# warship_demo_3.net
KiCad netlist of a schematic drawn in Altium Designer
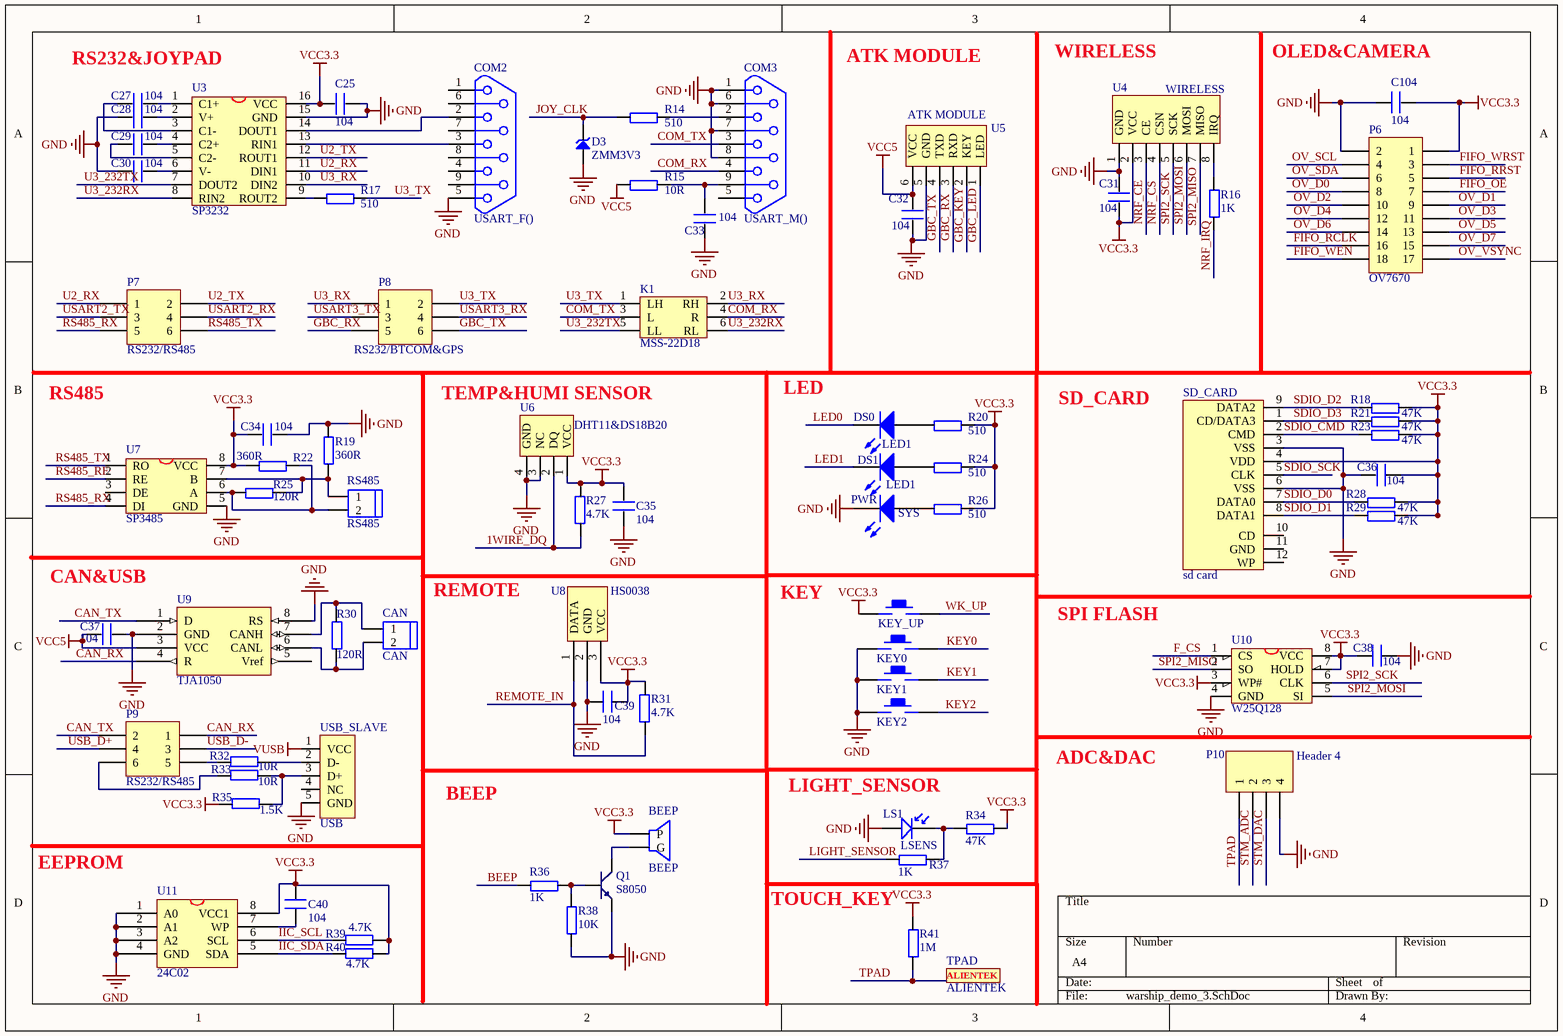
[diagram p0: warship_demo_3.SchDoc]

(export (version "E")
  (design (tool "Eeschema 10.0.6"))
  (components
    (comp (ref "BEEP")
      (value "BEEP")
      (footprint "BELL-5")
      (libsource (lib "WarShip V3 STM32103封装库") (part "BEEP"))
    )
    (comp (ref "C25") (value "104") (footprint "0603P") (libsource (lib "WarShip V3 STM32103封装库") (part "C")))
    (comp (ref "C27") (value "104") (footprint "0603P") (libsource (lib "WarShip V3 STM32103封装库") (part "C")))
    (comp (ref "C28") (value "104") (footprint "0603P") (libsource (lib "WarShip V3 STM32103封装库") (part "C")))
    (comp (ref "C29") (value "104") (footprint "0603P") (libsource (lib "WarShip V3 STM32103封装库") (part "C")))
    (comp (ref "C30") (value "104") (footprint "0603P") (libsource (lib "WarShip V3 STM32103封装库") (part "C")))
    (comp (ref "C31") (value "104") (footprint "0603P") (libsource (lib "WarShip V3 STM32103封装库") (part "C")))
    (comp (ref "C32") (value "104") (footprint "0603P") (libsource (lib "WarShip V3 STM32103封装库") (part "C")))
    (comp (ref "C33") (value "104") (footprint "0603P") (libsource (lib "WarShip V3 STM32103封装库") (part "C")))
    (comp (ref "C34") (value "104") (footprint "0603P") (libsource (lib "WarShip V3 STM32103封装库") (part "C")))
    (comp (ref "C35") (value "104") (footprint "0603P") (libsource (lib "WarShip V3 STM32103封装库") (part "C")))
    (comp (ref "C36") (value "104") (footprint "0603P") (libsource (lib "WarShip V3 STM32103封装库") (part "C")))
    (comp (ref "C37") (value "104") (footprint "0603P") (libsource (lib "WarShip V3 STM32103封装库") (part "C")))
    (comp (ref "C38") (value "104") (footprint "0603P") (libsource (lib "WarShip V3 STM32103封装库") (part "C")))
    (comp (ref "C39") (value "104") (footprint "0603P") (libsource (lib "WarShip V3 STM32103封装库") (part "C")))
    (comp (ref "C40") (value "104") (footprint "0603P") (libsource (lib "WarShip V3 STM32103封装库") (part "C")))
    (comp (ref "C104")
      (value "104")
      (footprint "0603P")
      (libsource (lib "WarShip V3 STM32103封装库") (part "C"))
    )
    (comp (ref "CAN")
      (value "CAN")
      (footprint "HEAD2L-0.8")
      (libsource (lib "WarShip V3 STM32103封装库") (part "HEAD2"))
    )
    (comp (ref "COM2")
      (value "USART_F()")
      (footprint "DB9")
      (libsource (lib "WarShip V3 STM32103封装库") (part "DB9"))
    )
    (comp (ref "COM3")
      (value "USART_M()")
      (footprint "DB9")
      (libsource (lib "WarShip V3 STM32103封装库") (part "DB9"))
    )
    (comp (ref "D3")
      (value "ZMM3V3")
      (footprint "DIODE_ZMMx")
      (description "ZMM3V6")
      (libsource (lib "WarShip V3 STM32103封装库") (part "ZMM3V6"))
    )
    (comp (ref "DS0")
      (value "LED1")
      (footprint "SMDLED")
      (description "Typical RED, GREEN, YELLOW, AMBER GaAs LED")
      (fields (field (name "PUBLISHER") "Altium Limited"))
      (libsource (lib "WarShip V3 STM32103封装库") (part "LED2"))
    )
    (comp (ref "DS1")
      (value "LED1")
      (footprint "SMDLED")
      (description "Typical RED, GREEN, YELLOW, AMBER GaAs LED")
      (fields (field (name "PUBLISHER") "Altium Limited"))
      (libsource (lib "WarShip V3 STM32103封装库") (part "LED2"))
    )
    (comp (ref "K1")
      (value "MSS-22D18")
      (footprint "MSS-22D18-DIP")
      (description "六脚波动开关")
      (libsource (lib "WarShip V3 STM32103封装库") (part "MSS-22D18"))
    )
    (comp (ref "KEY0")
      (value "KEY_UP")
      (footprint "KEY_M")
      (libsource (lib "WarShip V3 STM32103封装库") (part "KEY_M"))
    )
    (comp (ref "KEY1")
      (value "KEY_UP")
      (footprint "KEY_M")
      (libsource (lib "WarShip V3 STM32103封装库") (part "KEY_M"))
    )
    (comp (ref "KEY2")
      (value "KEY_UP")
      (footprint "KEY_M")
      (libsource (lib "WarShip V3 STM32103封装库") (part "KEY_M"))
    )
    (comp (ref "KEY_UP")
      (value "KEY_UP")
      (footprint "KEY_M")
      (libsource (lib "WarShip V3 STM32103封装库") (part "KEY_M"))
    )
    (comp (ref "LS1")
      (value "LSENS")
      (footprint "SMDLED")
      (description "LIGHT SENS")
      (libsource (lib "WarShip V3 STM32103封装库") (part "LSENS"))
    )
    (comp (ref "P6")
      (value "OV7670")
      (footprint "HDR2X9")
      (description "Header, 9-Pin, Dual row")
      (fields (field (name "PUBLISHER") "Altium Limited"))
      (libsource (lib "WarShip V3 STM32103封装库") (part "Header 9X2"))
    )
    (comp (ref "P7")
      (value "RS232/RS485")
      (footprint "HDR2X3")
      (description "Header, 3-Pin, Dual row")
      (fields (field (name "PUBLISHER") "Altium Limited"))
      (libsource (lib "WarShip V3 STM32103封装库") (part "Header 3X2"))
    )
    (comp (ref "P8")
      (value "RS232/BTCOM&GPS")
      (footprint "HDR2X3")
      (description "Header, 3-Pin, Dual row")
      (fields (field (name "PUBLISHER") "Altium Limited"))
      (libsource (lib "WarShip V3 STM32103封装库") (part "Header 3X2"))
    )
    (comp (ref "P9")
      (value "RS232/RS485")
      (footprint "HDR2X3")
      (description "Header, 3-Pin, Dual row")
      (fields (field (name "PUBLISHER") "Altium Limited"))
      (libsource (lib "") (part "Header 3X2_1"))
    )
    (comp (ref "P10")
      (value "Header 4")
      (footprint "HDR1X4")
      (description "Header, 4-Pin")
      (fields (field (name "PUBLISHER") "Altium Limited"))
      (libsource (lib "WarShip V3 STM32103封装库") (part "Header 4"))
    )
    (comp (ref "PWR")
      (value "SYS")
      (footprint "SMDLED")
      (description "Typical RED, GREEN, YELLOW, AMBER GaAs LED")
      (fields (field (name "PUBLISHER") "Altium Limited"))
      (libsource (lib "WarShip V3 STM32103封装库") (part "LED2"))
    )
    (comp (ref "Q1")
      (value "S8050")
      (footprint "SOT-23R")
      (description "8050/BCW846/BCW847")
      (libsource (lib "WarShip V3 STM32103封装库") (part "NPN"))
    )
    (comp (ref "R14") (value "510") (footprint "0603P") (libsource (lib "WarShip V3 STM32103封装库") (part "R")))
    (comp (ref "R15") (value "10R") (footprint "0603P") (libsource (lib "WarShip V3 STM32103封装库") (part "R")))
    (comp (ref "R16") (value "1K") (footprint "0603P") (libsource (lib "WarShip V3 STM32103封装库") (part "R")))
    (comp (ref "R17") (value "510") (footprint "0603P") (libsource (lib "WarShip V3 STM32103封装库") (part "R")))
    (comp (ref "R18") (value "47K") (footprint "0603P") (libsource (lib "WarShip V3 STM32103封装库") (part "R")))
    (comp (ref "R19")
      (value "360R")
      (footprint "0603P")
      (libsource (lib "WarShip V3 STM32103封装库") (part "R"))
    )
    (comp (ref "R20") (value "510") (footprint "0603P") (libsource (lib "WarShip V3 STM32103封装库") (part "R")))
    (comp (ref "R21") (value "47K") (footprint "0603P") (libsource (lib "WarShip V3 STM32103封装库") (part "R")))
    (comp (ref "R22")
      (value "360R")
      (footprint "0603P")
      (libsource (lib "WarShip V3 STM32103封装库") (part "R"))
    )
    (comp (ref "R23") (value "47K") (footprint "0603P") (libsource (lib "WarShip V3 STM32103封装库") (part "R")))
    (comp (ref "R24") (value "510") (footprint "0603P") (libsource (lib "WarShip V3 STM32103封装库") (part "R")))
    (comp (ref "R25")
      (value "120R")
      (footprint "0603P")
      (libsource (lib "WarShip V3 STM32103封装库") (part "R"))
    )
    (comp (ref "R26") (value "510") (footprint "0603P") (libsource (lib "WarShip V3 STM32103封装库") (part "R")))
    (comp (ref "R27")
      (value "4.7K")
      (footprint "0603P")
      (libsource (lib "WarShip V3 STM32103封装库") (part "R"))
    )
    (comp (ref "R28") (value "47K") (footprint "0603P") (libsource (lib "WarShip V3 STM32103封装库") (part "R")))
    (comp (ref "R29") (value "47K") (footprint "0603P") (libsource (lib "WarShip V3 STM32103封装库") (part "R")))
    (comp (ref "R30")
      (value "120R")
      (footprint "0603P")
      (libsource (lib "WarShip V3 STM32103封装库") (part "R"))
    )
    (comp (ref "R31")
      (value "4.7K")
      (footprint "0603P")
      (libsource (lib "WarShip V3 STM32103封装库") (part "R"))
    )
    (comp (ref "R32") (value "10R") (footprint "0603P") (libsource (lib "WarShip V3 STM32103封装库") (part "R")))
    (comp (ref "R33") (value "10R") (footprint "0603P") (libsource (lib "WarShip V3 STM32103封装库") (part "R")))
    (comp (ref "R34") (value "47K") (footprint "0603P") (libsource (lib "WarShip V3 STM32103封装库") (part "R")))
    (comp (ref "R35")
      (value "1.5K")
      (footprint "0603P")
      (libsource (lib "WarShip V3 STM32103封装库") (part "R"))
    )
    (comp (ref "R36") (value "1K") (footprint "0603P") (libsource (lib "WarShip V3 STM32103封装库") (part "R")))
    (comp (ref "R37") (value "1K") (footprint "0603P") (libsource (lib "WarShip V3 STM32103封装库") (part "R")))
    (comp (ref "R38") (value "10K") (footprint "0603P") (libsource (lib "WarShip V3 STM32103封装库") (part "R")))
    (comp (ref "R39")
      (value "4.7K")
      (footprint "0603P")
      (libsource (lib "WarShip V3 STM32103封装库") (part "R"))
    )
    (comp (ref "R40")
      (value "4.7K")
      (footprint "0603P")
      (libsource (lib "WarShip V3 STM32103封装库") (part "R"))
    )
    (comp (ref "R41") (value "1M") (footprint "0603P") (libsource (lib "WarShip V3 STM32103封装库") (part "R")))
    (comp (ref "RS485")
      (value "RS485")
      (footprint "HEAD2L-0.8")
      (libsource (lib "WarShip V3 STM32103封装库") (part "HEAD2"))
    )
    (comp (ref "SD_CARD")
      (value "sd card")
      (footprint "SDCARD_L")
      (libsource (lib "WarShip V3 STM32103封装库") (part "sd card"))
    )
    (comp (ref "TPAD")
      (value "ALIENTEK")
      (footprint "ALIENTEK_PAD1")
      (libsource (lib "WarShip V3 STM32103封装库") (part "ALIENTEK"))
    )
    (comp (ref "U3")
      (value "SP3232")
      (footprint "SOP16M")
      (libsource (lib "WarShip V3 STM32103封装库") (part "MAX3232"))
    )
    (comp (ref "U4")
      (value "WIRELESS")
      (footprint "NRF24L01")
      (libsource (lib "WarShip V3 STM32103封装库") (part "NRF24L01"))
    )
    (comp (ref "U5")
      (value "ATK MODULE")
      (footprint "HEAD6")
      (description "ATK-HC05")
      (libsource (lib "WarShip V3 STM32103封装库") (part "ATK-HC05"))
    )
    (comp (ref "U6")
      (value "DHT11&DS18B20")
      (footprint "DHT11")
      (description "数字温湿度传感器")
      (libsource (lib "WarShip V3 STM32103封装库") (part "DHT11"))
    )
    (comp (ref "U7")
      (value "SP3485")
      (footprint "SOP-8")
      (libsource (lib "WarShip V3 STM32103封装库") (part "MAX3485"))
    )
    (comp (ref "U8")
      (value "HS0038")
      (footprint "HS0038")
      (libsource (lib "WarShip V3 STM32103封装库") (part "HS0038"))
    )
    (comp (ref "U9")
      (value "TJA1050")
      (footprint "SOP-8")
      (libsource (lib "WarShip V3 STM32103封装库") (part "SN65HVD230D"))
    )
    (comp (ref "U10")
      (value "W25Q128")
      (footprint "SOIC-8")
      (description "W25X16;SST25VF016;MX25L1605")
      (libsource (lib "WarShip V3 STM32103封装库") (part "W25X16"))
    )
    (comp (ref "U11")
      (value "24C02")
      (footprint "SOP-8")
      (libsource (lib "WarShip V3 STM32103封装库") (part "24C256"))
    )
    (comp (ref "USB_SLAVE")
      (value "USB")
      (footprint "USB/SM0.8-6H5")
      (libsource (lib "WarShip V3 STM32103封装库") (part "USB5"))
    )
  )
  (nets
    (net (code "1") (name "/1WIRE_DQ") (class "Default")
      (node (ref "R27") (pin "2") (pintype "passive"))
      (node (ref "U6") (pin "2") (pinfunction "DQ_2") (pintype "passive"))
    )
    (net (code "2") (name "/BEEP") (class "Default") (node (ref "R36") (pin "1") (pintype "passive")))
    (net (code "3") (name "/CAN_RX") (class "Default")
      (node (ref "P9") (pin "1") (pinfunction "1_1") (pintype "passive"))
      (node (ref "U9") (pin "4") (pinfunction "R_4") (pintype "output"))
    )
    (net (code "4") (name "/CAN_TX") (class "Default")
      (node (ref "P9") (pin "2") (pinfunction "2_2") (pintype "passive"))
      (node (ref "U9") (pin "1") (pinfunction "D_1") (pintype "input"))
    )
    (net (code "5") (name "/COM_RX") (class "Default")
      (node (ref "COM3") (pin "4") (pinfunction "4_4") (pintype "passive"))
      (node (ref "K1") (pin "4") (pinfunction "R_4") (pintype "passive"))
    )
    (net (code "6") (name "/COM_TX") (class "Default")
      (node (ref "COM3") (pin "3") (pinfunction "3_3") (pintype "passive"))
      (node (ref "K1") (pin "3") (pinfunction "L_3") (pintype "passive"))
    )
    (net (code "7") (name "/FIFO_OE") (class "Default")
      (node (ref "P6") (pin "7") (pinfunction "7_7") (pintype "passive"))
    )
    (net (code "8") (name "/FIFO_RCLK") (class "Default")
      (node (ref "P6") (pin "16") (pinfunction "16_16") (pintype "passive"))
    )
    (net (code "9") (name "/FIFO_RRST") (class "Default")
      (node (ref "P6") (pin "5") (pinfunction "5_5") (pintype "passive"))
    )
    (net (code "10") (name "/FIFO_WEN") (class "Default")
      (node (ref "P6") (pin "18") (pinfunction "18_18") (pintype "passive"))
    )
    (net (code "11") (name "/FIFO_WRST") (class "Default")
      (node (ref "P6") (pin "3") (pinfunction "3_3") (pintype "passive"))
    )
    (net (code "12") (name "/F_CS") (class "Default")
      (node (ref "U10") (pin "1") (pinfunction "CS_1") (pintype "passive"))
    )
    (net (code "13") (name "/GBC_KEY") (class "Default")
      (node (ref "U5") (pin "2") (pinfunction "KEY_2") (pintype "passive"))
    )
    (net (code "14") (name "/GBC_LED") (class "Default")
      (node (ref "U5") (pin "1") (pinfunction "LED_1") (pintype "passive"))
    )
    (net (code "15") (name "/GBC_RX") (class "Default")
      (node (ref "P8") (pin "5") (pinfunction "5_5") (pintype "passive"))
      (node (ref "U5") (pin "3") (pinfunction "RXD_3") (pintype "passive"))
    )
    (net (code "16") (name "/GBC_TX") (class "Default")
      (node (ref "P8") (pin "6") (pinfunction "6_6") (pintype "passive"))
      (node (ref "U5") (pin "4") (pinfunction "TXD_4") (pintype "passive"))
    )
    (net (code "17") (name "/IIC_SCL") (class "Default")
      (node (ref "R39") (pin "2") (pintype "passive"))
      (node (ref "U11") (pin "6") (pinfunction "SCL_6") (pintype "passive"))
    )
    (net (code "18") (name "/IIC_SDA") (class "Default")
      (node (ref "R40") (pin "2") (pintype "passive"))
      (node (ref "U11") (pin "5") (pinfunction "SDA_5") (pintype "passive"))
    )
    (net (code "19") (name "/JOY_CLK") (class "Default")
      (node (ref "D3") (pin "2") (pintype "passive"))
      (node (ref "R14") (pin "1") (pintype "passive"))
    )
    (net (code "20") (name "/KEY0") (class "Default")
      (node (ref "KEY0") (pin "2") (pinfunction "2_2") (pintype "passive"))
    )
    (net (code "21") (name "/KEY1") (class "Default")
      (node (ref "KEY1") (pin "2") (pinfunction "2_2") (pintype "passive"))
    )
    (net (code "22") (name "/KEY2") (class "Default")
      (node (ref "KEY2") (pin "2") (pinfunction "2_2") (pintype "passive"))
    )
    (net (code "23") (name "/LED0") (class "Default")
      (node (ref "DS0") (pin "2") (pinfunction "K_2") (pintype "passive"))
    )
    (net (code "24") (name "/LED1") (class "Default")
      (node (ref "DS1") (pin "2") (pinfunction "K_2") (pintype "passive"))
    )
    (net (code "25") (name "/LIGHT_SENSOR") (class "Default")
      (node (ref "R37") (pin "1") (pintype "passive"))
    )
    (net (code "26") (name "/NRF_CE") (class "Default")
      (node (ref "U4") (pin "3") (pinfunction "CE_3") (pintype "passive"))
    )
    (net (code "27") (name "/NRF_CS") (class "Default")
      (node (ref "U4") (pin "4") (pinfunction "CSN_4") (pintype "passive"))
    )
    (net (code "28") (name "/NRF_IRQ") (class "Default") (node (ref "R16") (pin "1") (pintype "passive")))
    (net (code "29") (name "/OV_D0") (class "Default")
      (node (ref "P6") (pin "8") (pinfunction "8_8") (pintype "passive"))
    )
    (net (code "30") (name "/OV_D1") (class "Default")
      (node (ref "P6") (pin "9") (pinfunction "9_9") (pintype "passive"))
    )
    (net (code "31") (name "/OV_D2") (class "Default")
      (node (ref "P6") (pin "10") (pinfunction "10_10") (pintype "passive"))
    )
    (net (code "32") (name "/OV_D3") (class "Default")
      (node (ref "P6") (pin "11") (pinfunction "11_11") (pintype "passive"))
    )
    (net (code "33") (name "/OV_D4") (class "Default")
      (node (ref "P6") (pin "12") (pinfunction "12_12") (pintype "passive"))
    )
    (net (code "34") (name "/OV_D5") (class "Default")
      (node (ref "P6") (pin "13") (pinfunction "13_13") (pintype "passive"))
    )
    (net (code "35") (name "/OV_D6") (class "Default")
      (node (ref "P6") (pin "14") (pinfunction "14_14") (pintype "passive"))
    )
    (net (code "36") (name "/OV_D7") (class "Default")
      (node (ref "P6") (pin "15") (pinfunction "15_15") (pintype "passive"))
    )
    (net (code "37") (name "/OV_SCL") (class "Default")
      (node (ref "P6") (pin "4") (pinfunction "4_4") (pintype "passive"))
    )
    (net (code "38") (name "/OV_SDA") (class "Default")
      (node (ref "P6") (pin "6") (pinfunction "6_6") (pintype "passive"))
    )
    (net (code "39") (name "/OV_VSYNC") (class "Default")
      (node (ref "P6") (pin "17") (pinfunction "17_17") (pintype "passive"))
    )
    (net (code "40") (name "/REMOTE_IN") (class "Default")
      (node (ref "R31") (pin "2") (pintype "passive"))
      (node (ref "U8") (pin "1") (pinfunction "DATA_1") (pintype "passive"))
    )
    (net (code "41") (name "/RS485_RE") (class "Default")
      (node (ref "U7") (pin "2") (pinfunction "RE_2") (pintype "passive"))
    )
    (net (code "42") (name "/RS485_RX") (class "Default")
      (node (ref "P7") (pin "5") (pinfunction "5_5") (pintype "passive"))
      (node (ref "U7") (pin "4") (pinfunction "DI_4") (pintype "passive"))
    )
    (net (code "43") (name "/RS485_TX") (class "Default")
      (node (ref "P7") (pin "6") (pinfunction "6_6") (pintype "passive"))
      (node (ref "U7") (pin "1") (pinfunction "RO_1") (pintype "passive"))
    )
    (net (code "44") (name "/SDIO_CMD") (class "Default")
      (node (ref "R23") (pin "1") (pintype "passive"))
      (node (ref "SD_CARD") (pin "2") (pinfunction "CMD_2") (pintype "passive"))
    )
    (net (code "45") (name "/SDIO_D0") (class "Default")
      (node (ref "R28") (pin "1") (pintype "passive"))
      (node (ref "SD_CARD") (pin "7") (pinfunction "DATA0_7") (pintype "passive"))
    )
    (net (code "46") (name "/SDIO_D1") (class "Default")
      (node (ref "R29") (pin "1") (pintype "passive"))
      (node (ref "SD_CARD") (pin "8") (pinfunction "DATA1_8") (pintype "passive"))
    )
    (net (code "47") (name "/SDIO_D2") (class "Default")
      (node (ref "R18") (pin "1") (pintype "passive"))
      (node (ref "SD_CARD") (pin "9") (pinfunction "DATA2_9") (pintype "passive"))
    )
    (net (code "48") (name "/SDIO_D3") (class "Default")
      (node (ref "R21") (pin "1") (pintype "passive"))
      (node (ref "SD_CARD") (pin "1") (pinfunction "CD/DATA3_1") (pintype "passive"))
    )
    (net (code "49") (name "/SDIO_SCK") (class "Default")
      (node (ref "SD_CARD") (pin "5") (pinfunction "CLK_5") (pintype "passive"))
    )
    (net (code "50") (name "/SPI2_MISO") (class "Default")
      (node (ref "U10") (pin "2") (pinfunction "SO_2") (pintype "passive"))
      (node (ref "U4") (pin "7") (pinfunction "MISO_7") (pintype "passive"))
    )
    (net (code "51") (name "/SPI2_MOSI") (class "Default")
      (node (ref "U10") (pin "5") (pinfunction "SI_5") (pintype "passive"))
      (node (ref "U4") (pin "6") (pinfunction "MOSI_6") (pintype "passive"))
    )
    (net (code "52") (name "/SPI2_SCK") (class "Default")
      (node (ref "U10") (pin "6") (pinfunction "CLK_6") (pintype "passive"))
      (node (ref "U4") (pin "5") (pinfunction "SCK_5") (pintype "passive"))
    )
    (net (code "53") (name "/STM_ADC") (class "Default")
      (node (ref "P10") (pin "2") (pinfunction "2_2") (pintype "passive"))
    )
    (net (code "54") (name "/STM_DAC") (class "Default")
      (node (ref "P10") (pin "3") (pinfunction "3_3") (pintype "passive"))
    )
    (net (code "55") (name "/TPAD") (class "Default")
      (node (ref "P10") (pin "1") (pinfunction "1_1") (pintype "passive"))
      (node (ref "R41") (pin "1") (pintype "passive"))
    )
    (net (code "56") (name "/U2_RX") (class "Default")
      (node (ref "P7") (pin "1") (pinfunction "1_1") (pintype "passive"))
      (node (ref "U3") (pin "11") (pinfunction "DIN1_11") (pintype "passive"))
    )
    (net (code "57") (name "/U2_TX") (class "Default")
      (node (ref "P7") (pin "2") (pinfunction "2_2") (pintype "passive"))
      (node (ref "U3") (pin "12") (pinfunction "ROUT1_12") (pintype "passive"))
    )
    (net (code "58") (name "/U3_232RX") (class "Default")
      (node (ref "K1") (pin "6") (pinfunction "RL_6") (pintype "passive"))
      (node (ref "U3") (pin "8") (pinfunction "RIN2_8") (pintype "passive"))
    )
    (net (code "59") (name "/U3_232TX") (class "Default")
      (node (ref "K1") (pin "5") (pinfunction "LL_5") (pintype "passive"))
      (node (ref "U3") (pin "7") (pinfunction "DOUT2_7") (pintype "passive"))
    )
    (net (code "60") (name "/U3_RX") (class "Default")
      (node (ref "K1") (pin "2") (pinfunction "RH_2") (pintype "passive"))
      (node (ref "P8") (pin "1") (pinfunction "1_1") (pintype "passive"))
      (node (ref "U3") (pin "10") (pinfunction "DIN2_10") (pintype "passive"))
    )
    (net (code "61") (name "/U3_TX") (class "Default")
      (node (ref "K1") (pin "1") (pinfunction "LH_1") (pintype "passive"))
      (node (ref "P8") (pin "2") (pinfunction "2_2") (pintype "passive"))
      (node (ref "R17") (pin "2") (pintype "passive"))
    )
    (net (code "62") (name "/USART2_RX") (class "Default")
      (node (ref "P7") (pin "4") (pinfunction "4_4") (pintype "passive"))
    )
    (net (code "63") (name "/USART2_TX") (class "Default")
      (node (ref "P7") (pin "3") (pinfunction "3_3") (pintype "passive"))
    )
    (net (code "64") (name "/USART3_RX") (class "Default")
      (node (ref "P8") (pin "4") (pinfunction "4_4") (pintype "passive"))
    )
    (net (code "65") (name "/USART3_TX") (class "Default")
      (node (ref "P8") (pin "3") (pinfunction "3_3") (pintype "passive"))
    )
    (net (code "66") (name "/USB_D+") (class "Default")
      (node (ref "P9") (pin "4") (pinfunction "4_4") (pintype "passive"))
    )
    (net (code "67") (name "/USB_D-") (class "Default")
      (node (ref "P9") (pin "3") (pinfunction "3_3") (pintype "passive"))
    )
    (net (code "68") (name "/WK_UP") (class "Default")
      (node (ref "KEY_UP") (pin "2") (pinfunction "2_2") (pintype "passive"))
    )
    (net (code "69") (name "GND") (class "Default")
      (node (ref "C104") (pin "2") (pintype "passive"))
      (node (ref "C25") (pin "1") (pintype "passive"))
      (node (ref "C28") (pin "2") (pintype "passive"))
      (node (ref "C30") (pin "2") (pintype "passive"))
      (node (ref "C31") (pin "2") (pintype "passive"))
      (node (ref "C32") (pin "1") (pintype "passive"))
      (node (ref "C33") (pin "2") (pintype "passive"))
      (node (ref "C34") (pin "1") (pintype "passive"))
      (node (ref "C35") (pin "2") (pintype "passive"))
      (node (ref "C36") (pin "2") (pintype "passive"))
      (node (ref "C37") (pin "1") (pintype "passive"))
      (node (ref "C38") (pin "1") (pintype "passive"))
      (node (ref "C39") (pin "1") (pintype "passive"))
      (node (ref "COM2") (pin "5") (pinfunction "5_5") (pintype "passive"))
      (node (ref "COM3") (pin "1") (pinfunction "1_1") (pintype "passive"))
      (node (ref "COM3") (pin "6") (pinfunction "6_6") (pintype "passive"))
      (node (ref "COM3") (pin "7") (pinfunction "7_7") (pintype "passive"))
      (node (ref "COM3") (pin "8") (pinfunction "8_8") (pintype "passive"))
      (node (ref "D3") (pin "1") (pintype "passive"))
      (node (ref "KEY0") (pin "1") (pinfunction "1_1") (pintype "passive"))
      (node (ref "KEY1") (pin "1") (pinfunction "1_1") (pintype "passive"))
      (node (ref "KEY2") (pin "1") (pinfunction "1_1") (pintype "passive"))
      (node (ref "LS1") (pin "1") (pinfunction "1_1") (pintype "passive"))
      (node (ref "P10") (pin "4") (pinfunction "4_4") (pintype "passive"))
      (node (ref "P6") (pin "2") (pinfunction "2_2") (pintype "passive"))
      (node (ref "PWR") (pin "2") (pinfunction "K_2") (pintype "passive"))
      (node (ref "Q1") (pin "1") (pinfunction "E_1") (pintype "passive"))
      (node (ref "R19") (pin "2") (pintype "passive"))
      (node (ref "R38") (pin "1") (pintype "passive"))
      (node (ref "SD_CARD") (pin "3") (pinfunction "VSS_3") (pintype "passive"))
      (node (ref "SD_CARD") (pin "6") (pinfunction "VSS_6") (pintype "passive"))
      (node (ref "U10") (pin "4") (pinfunction "GND_4") (pintype "passive"))
      (node (ref "U11") (pin "1") (pinfunction "A0_1") (pintype "passive"))
      (node (ref "U11") (pin "2") (pinfunction "A1_2") (pintype "passive"))
      (node (ref "U11") (pin "3") (pinfunction "A2_3") (pintype "passive"))
      (node (ref "U11") (pin "4") (pinfunction "GND_4") (pintype "passive"))
      (node (ref "U3") (pin "15") (pinfunction "GND_15") (pintype "passive"))
      (node (ref "U4") (pin "1") (pinfunction "GND_1") (pintype "passive"))
      (node (ref "U5") (pin "5") (pinfunction "GND_5") (pintype "passive"))
      (node (ref "U6") (pin "3") (pinfunction "NC_3") (pintype "passive"))
      (node (ref "U6") (pin "4") (pinfunction "GND_4") (pintype "passive"))
      (node (ref "U7") (pin "5") (pinfunction "GND_5") (pintype "passive"))
      (node (ref "U8") (pin "2") (pinfunction "GND_2") (pintype "passive"))
      (node (ref "U9") (pin "2") (pinfunction "GND_2") (pintype "power_in"))
      (node (ref "U9") (pin "8") (pinfunction "RS_8") (pintype "input"))
      (node (ref "USB_SLAVE") (pin "5") (pinfunction "GND_5") (pintype "passive"))
    )
    (net (code "70") (name "Net-(BEEP-G)") (class "Default")
      (node (ref "BEEP") (pin "2") (pinfunction "G_2") (pintype "passive"))
      (node (ref "Q1") (pin "3") (pinfunction "C_3") (pintype "passive"))
    )
    (net (code "71") (name "Net-(C33-Pad1)") (class "Default")
      (node (ref "C33") (pin "1") (pintype "passive"))
      (node (ref "COM3") (pin "9") (pinfunction "9_9") (pintype "passive"))
      (node (ref "R15") (pin "2") (pintype "passive"))
    )
    (net (code "72") (name "Net-(COM3-Pad2)") (class "Default")
      (node (ref "COM3") (pin "2") (pinfunction "2_2") (pintype "passive"))
      (node (ref "R14") (pin "2") (pintype "passive"))
    )
    (net (code "73") (name "Net-(DS0-A)") (class "Default")
      (node (ref "DS0") (pin "1") (pinfunction "A_1") (pintype "passive"))
      (node (ref "R20") (pin "1") (pintype "passive"))
    )
    (net (code "74") (name "Net-(DS1-A)") (class "Default")
      (node (ref "DS1") (pin "1") (pinfunction "A_1") (pintype "passive"))
      (node (ref "R24") (pin "1") (pintype "passive"))
    )
    (net (code "75") (name "Net-(LS1-Pad2)") (class "Default")
      (node (ref "LS1") (pin "2") (pinfunction "2_2") (pintype "passive"))
      (node (ref "R34") (pin "1") (pintype "passive"))
      (node (ref "R37") (pin "2") (pintype "passive"))
    )
    (net (code "76") (name "Net-(P9-Pad5)") (class "Default")
      (node (ref "P9") (pin "5") (pinfunction "5_5") (pintype "passive"))
      (node (ref "R32") (pin "2") (pintype "passive"))
    )
    (net (code "77") (name "Net-(P9-Pad6)") (class "Default")
      (node (ref "P9") (pin "6") (pinfunction "6_6") (pintype "passive"))
      (node (ref "R33") (pin "2") (pintype "passive"))
    )
    (net (code "78") (name "Net-(PWR-A)") (class "Default")
      (node (ref "PWR") (pin "1") (pinfunction "A_1") (pintype "passive"))
      (node (ref "R26") (pin "1") (pintype "passive"))
    )
    (net (code "79") (name "Net-(Q1-B)") (class "Default")
      (node (ref "Q1") (pin "2") (pinfunction "B_2") (pintype "passive"))
      (node (ref "R36") (pin "2") (pintype "passive"))
      (node (ref "R38") (pin "2") (pintype "passive"))
    )
    (net (code "80") (name "Net-(U3-C1+)") (class "Default")
      (node (ref "C27") (pin "1") (pintype "passive"))
      (node (ref "U3") (pin "1") (pinfunction "C1+_1") (pintype "passive"))
    )
    (net (code "81") (name "Net-(U3-C1-)") (class "Default")
      (node (ref "C27") (pin "2") (pintype "passive"))
      (node (ref "U3") (pin "3") (pinfunction "C1-_3") (pintype "passive"))
    )
    (net (code "82") (name "Net-(U3-C2+)") (class "Default")
      (node (ref "C29") (pin "1") (pintype "passive"))
      (node (ref "U3") (pin "4") (pinfunction "C2+_4") (pintype "passive"))
    )
    (net (code "83") (name "Net-(U3-C2-)") (class "Default")
      (node (ref "C29") (pin "2") (pintype "passive"))
      (node (ref "U3") (pin "5") (pinfunction "C2-_5") (pintype "passive"))
    )
    (net (code "84") (name "Net-(U3-DOUT1)") (class "Default")
      (node (ref "COM2") (pin "2") (pinfunction "2_2") (pintype "passive"))
      (node (ref "U3") (pin "14") (pinfunction "DOUT1_14") (pintype "passive"))
    )
    (net (code "85") (name "Net-(U3-RIN1)") (class "Default")
      (node (ref "COM2") (pin "3") (pinfunction "3_3") (pintype "passive"))
      (node (ref "U3") (pin "13") (pinfunction "RIN1_13") (pintype "passive"))
    )
    (net (code "86") (name "Net-(U3-ROUT2)") (class "Default")
      (node (ref "R17") (pin "1") (pintype "passive"))
      (node (ref "U3") (pin "9") (pinfunction "ROUT2_9") (pintype "passive"))
    )
    (net (code "87") (name "Net-(U3-V+)") (class "Default")
      (node (ref "C28") (pin "1") (pintype "passive"))
      (node (ref "U3") (pin "2") (pinfunction "V+_2") (pintype "passive"))
    )
    (net (code "88") (name "Net-(U3-V-)") (class "Default")
      (node (ref "C30") (pin "1") (pintype "passive"))
      (node (ref "U3") (pin "6") (pinfunction "V-_6") (pintype "passive"))
    )
    (net (code "89") (name "Net-(U4-IRQ)") (class "Default")
      (node (ref "R16") (pin "2") (pintype "passive"))
      (node (ref "U4") (pin "8") (pinfunction "IRQ_8") (pintype "passive"))
    )
    (net (code "90") (name "Net-(U7-A)") (class "Default")
      (node (ref "R22") (pin "2") (pintype "passive"))
      (node (ref "R25") (pin "1") (pintype "passive"))
      (node (ref "RS485") (pin "2") (pinfunction "2_2") (pintype "passive"))
      (node (ref "U7") (pin "6") (pinfunction "A_6") (pintype "passive"))
    )
    (net (code "91") (name "Net-(U7-B)") (class "Default")
      (node (ref "R19") (pin "1") (pintype "passive"))
      (node (ref "R25") (pin "2") (pintype "passive"))
      (node (ref "RS485") (pin "1") (pinfunction "1_1") (pintype "passive"))
      (node (ref "U7") (pin "7") (pinfunction "B_7") (pintype "passive"))
    )
    (net (code "92") (name "Net-(U9-CANH)") (class "Default")
      (node (ref "CAN") (pin "1") (pinfunction "1_1") (pintype "passive"))
      (node (ref "R30") (pin "2") (pintype "passive"))
      (node (ref "U9") (pin "7") (pinfunction "CANH_7") (pintype "bidirectional"))
    )
    (net (code "93") (name "Net-(U9-CANL)") (class "Default")
      (node (ref "CAN") (pin "2") (pinfunction "2_2") (pintype "passive"))
      (node (ref "R30") (pin "1") (pintype "passive"))
      (node (ref "U9") (pin "6") (pinfunction "CANL_6") (pintype "bidirectional"))
    )
    (net (code "94") (name "Net-(U11-WP)") (class "Default")
      (node (ref "C40") (pin "2") (pintype "passive"))
      (node (ref "U11") (pin "7") (pinfunction "WP_7") (pintype "passive"))
    )
    (net (code "95") (name "Net-(USB_SLAVE-D+)") (class "Default")
      (node (ref "R33") (pin "1") (pintype "passive"))
      (node (ref "R35") (pin "1") (pintype "passive"))
      (node (ref "USB_SLAVE") (pin "3") (pinfunction "D+_3") (pintype "passive"))
    )
    (net (code "96") (name "Net-(USB_SLAVE-D-)") (class "Default")
      (node (ref "R32") (pin "1") (pintype "passive"))
      (node (ref "USB_SLAVE") (pin "2") (pinfunction "D-_2") (pintype "passive"))
    )
    (net (code "97") (name "VCC3.3") (class "Default")
      (node (ref "BEEP") (pin "1") (pinfunction "P_1") (pintype "passive"))
      (node (ref "C104") (pin "1") (pintype "passive"))
      (node (ref "C25") (pin "2") (pintype "passive"))
      (node (ref "C31") (pin "1") (pintype "passive"))
      (node (ref "C34") (pin "2") (pintype "passive"))
      (node (ref "C35") (pin "1") (pintype "passive"))
      (node (ref "C36") (pin "1") (pintype "passive"))
      (node (ref "C38") (pin "2") (pintype "passive"))
      (node (ref "C39") (pin "2") (pintype "passive"))
      (node (ref "C40") (pin "1") (pintype "passive"))
      (node (ref "KEY_UP") (pin "1") (pinfunction "1_1") (pintype "passive"))
      (node (ref "P6") (pin "1") (pinfunction "1_1") (pintype "passive"))
      (node (ref "R18") (pin "2") (pintype "passive"))
      (node (ref "R20") (pin "2") (pintype "passive"))
      (node (ref "R21") (pin "2") (pintype "passive"))
      (node (ref "R22") (pin "1") (pintype "passive"))
      (node (ref "R23") (pin "2") (pintype "passive"))
      (node (ref "R24") (pin "2") (pintype "passive"))
      (node (ref "R26") (pin "2") (pintype "passive"))
      (node (ref "R27") (pin "1") (pintype "passive"))
      (node (ref "R28") (pin "2") (pintype "passive"))
      (node (ref "R29") (pin "2") (pintype "passive"))
      (node (ref "R31") (pin "1") (pintype "passive"))
      (node (ref "R34") (pin "2") (pintype "passive"))
      (node (ref "R35") (pin "2") (pintype "passive"))
      (node (ref "R39") (pin "1") (pintype "passive"))
      (node (ref "R40") (pin "1") (pintype "passive"))
      (node (ref "R41") (pin "2") (pintype "passive"))
      (node (ref "SD_CARD") (pin "4") (pinfunction "VDD_4") (pintype "passive"))
      (node (ref "U10") (pin "3") (pinfunction "WP#_3") (pintype "passive"))
      (node (ref "U10") (pin "7") (pinfunction "HOLD_7") (pintype "passive"))
      (node (ref "U10") (pin "8") (pinfunction "VCC_8") (pintype "passive"))
      (node (ref "U11") (pin "8") (pinfunction "VCC1_8") (pintype "passive"))
      (node (ref "U3") (pin "16") (pinfunction "VCC_16") (pintype "passive"))
      (node (ref "U4") (pin "2") (pinfunction "VCC_2") (pintype "passive"))
      (node (ref "U6") (pin "1") (pinfunction "VCC_1") (pintype "passive"))
      (node (ref "U7") (pin "8") (pinfunction "VCC_8") (pintype "passive"))
      (node (ref "U8") (pin "3") (pinfunction "VCC_3") (pintype "passive"))
    )
    (net (code "98") (name "VCC5") (class "Default")
      (node (ref "C32") (pin "2") (pintype "passive"))
      (node (ref "C37") (pin "2") (pintype "passive"))
      (node (ref "R15") (pin "1") (pintype "passive"))
      (node (ref "U5") (pin "6") (pinfunction "VCC_6") (pintype "passive"))
      (node (ref "U9") (pin "3") (pinfunction "VCC_3") (pintype "power_in"))
    )
    (net (code "99") (name "VUSB") (class "Default")
      (node (ref "USB_SLAVE") (pin "1") (pinfunction "VCC_1") (pintype "passive"))
    )
    (net (code "100") (name "unconnected-(COM2-Pad1)") (class "Default")
      (node (ref "COM2") (pin "1") (pinfunction "1_1") (pintype "passive"))
    )
    (net (code "101") (name "unconnected-(COM2-Pad4)") (class "Default")
      (node (ref "COM2") (pin "4") (pinfunction "4_4") (pintype "passive"))
    )
    (net (code "102") (name "unconnected-(COM2-Pad6)") (class "Default")
      (node (ref "COM2") (pin "6") (pinfunction "6_6") (pintype "passive"))
    )
    (net (code "103") (name "unconnected-(COM2-Pad7)") (class "Default")
      (node (ref "COM2") (pin "7") (pinfunction "7_7") (pintype "passive"))
    )
    (net (code "104") (name "unconnected-(COM2-Pad8)") (class "Default")
      (node (ref "COM2") (pin "8") (pinfunction "8_8") (pintype "passive"))
    )
    (net (code "105") (name "unconnected-(COM2-Pad9)") (class "Default")
      (node (ref "COM2") (pin "9") (pinfunction "9_9") (pintype "passive"))
    )
    (net (code "106") (name "unconnected-(COM3-Pad5)") (class "Default")
      (node (ref "COM3") (pin "5") (pinfunction "5_5") (pintype "passive"))
    )
    (net (code "107") (name "unconnected-(SD_CARD-CD-Pad10)") (class "Default")
      (node (ref "SD_CARD") (pin "10") (pinfunction "CD_10") (pintype "passive"))
    )
    (net (code "108") (name "unconnected-(SD_CARD-GND-Pad11)") (class "Default")
      (node (ref "SD_CARD") (pin "11") (pinfunction "GND_11") (pintype "passive"))
    )
    (net (code "109") (name "unconnected-(SD_CARD-WP-Pad12)") (class "Default")
      (node (ref "SD_CARD") (pin "12") (pinfunction "WP_12") (pintype "passive"))
    )
    (net (code "110") (name "unconnected-(U7-DE-Pad3)") (class "Default")
      (node (ref "U7") (pin "3") (pinfunction "DE_3") (pintype "passive"))
    )
    (net (code "111") (name "unconnected-(U9-Vref-Pad5)") (class "Default")
      (node (ref "U9") (pin "5") (pinfunction "Vref_5") (pintype "output"))
    )
    (net (code "112") (name "unconnected-(USB_SLAVE-NC-Pad4)") (class "Default")
      (node (ref "USB_SLAVE") (pin "4") (pinfunction "NC_4") (pintype "passive"))
    )
  )
)
